# reed.net
KiCad netlist of a schematic drawn in EAGLE
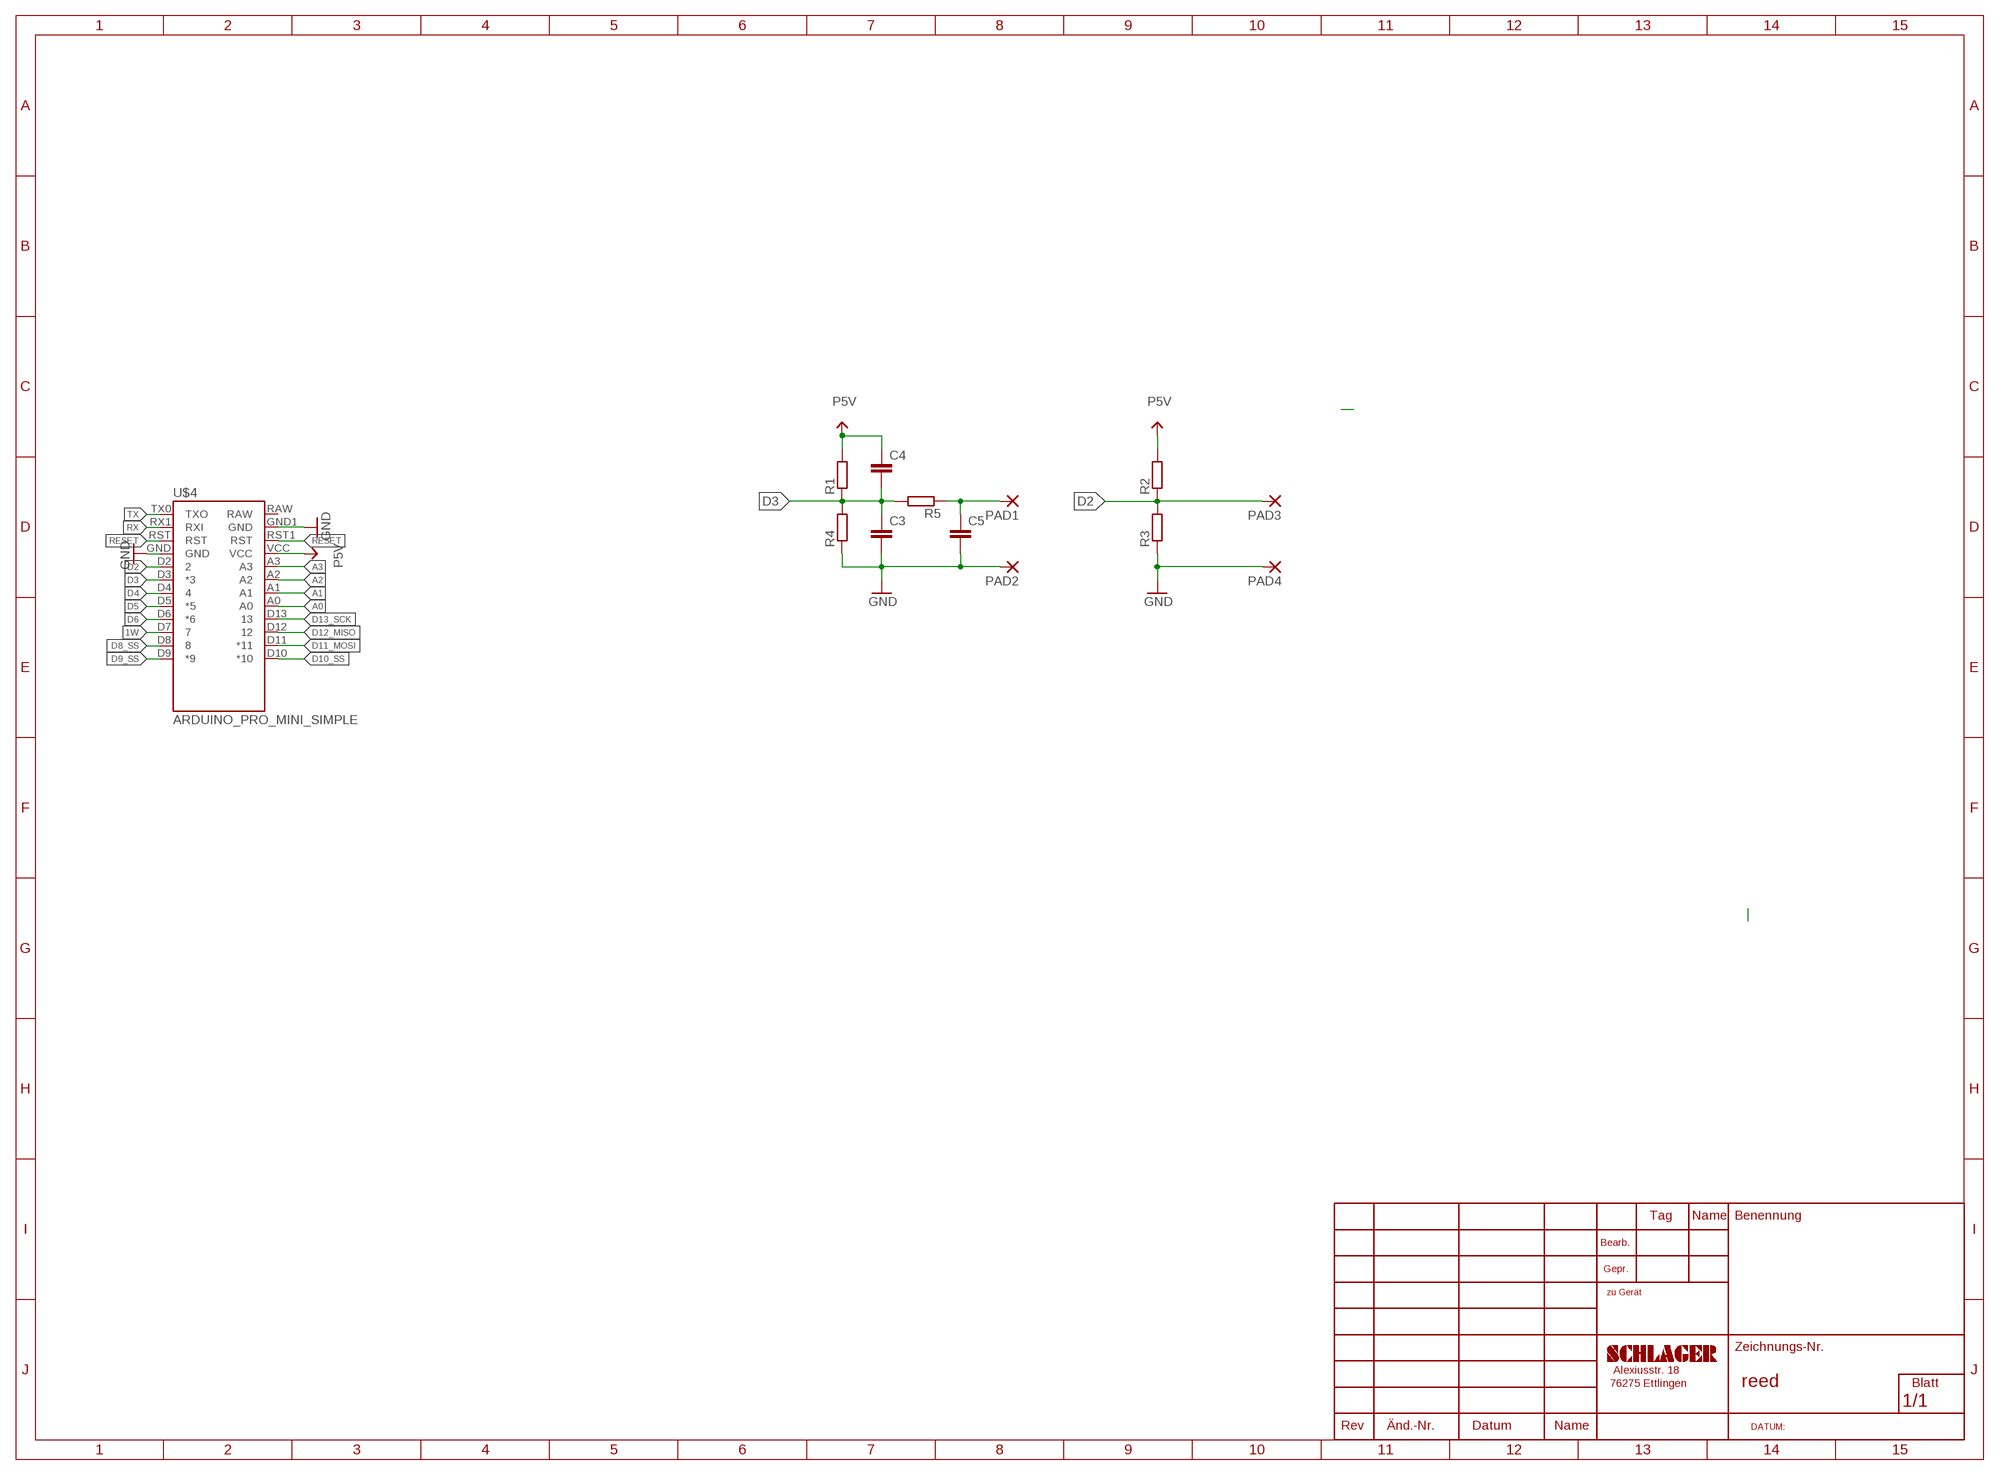
[diagram p0: schematic, sheet 1]

(export (version "E")
  (design (tool "Eeschema 10.0.6"))
  (components
    (comp (ref "C3")
      (value "C-EUC0603K")
      (footprint "eagle-import:C0603K")
      (libsource (lib "eagle-import") (part "C-EUC0603K"))
    )
    (comp (ref "C4")
      (value "C-EUC0603K")
      (footprint "eagle-import:C0603K")
      (libsource (lib "eagle-import") (part "C-EUC0603K"))
    )
    (comp (ref "C5")
      (value "C-EUC0603K")
      (footprint "eagle-import:C0603K")
      (libsource (lib "eagle-import") (part "C-EUC0603K"))
    )
    (comp (ref "PAD1")
      (value "SMD2")
      (footprint "eagle-import:SMD1,27-2,54")
      (libsource (lib "eagle-import") (part "SMD2"))
    )
    (comp (ref "PAD2")
      (value "SMD2")
      (footprint "eagle-import:SMD1,27-2,54")
      (libsource (lib "eagle-import") (part "SMD2"))
    )
    (comp (ref "PAD3")
      (value "SMD2")
      (footprint "eagle-import:SMD1,27-2,54")
      (libsource (lib "eagle-import") (part "SMD2"))
    )
    (comp (ref "PAD4")
      (value "SMD2")
      (footprint "eagle-import:SMD1,27-2,54")
      (libsource (lib "eagle-import") (part "SMD2"))
    )
    (comp (ref "R1")
      (value "R-EU_R0603")
      (footprint "eagle-import:R0603")
      (libsource (lib "eagle-import") (part "R-EU_R0603"))
    )
    (comp (ref "R2")
      (value "R-EU_R0603")
      (footprint "eagle-import:R0603")
      (libsource (lib "eagle-import") (part "R-EU_R0603"))
    )
    (comp (ref "R3")
      (value "R-EU_R0603")
      (footprint "eagle-import:R0603")
      (libsource (lib "eagle-import") (part "R-EU_R0603"))
    )
    (comp (ref "R4")
      (value "R-EU_R0603")
      (footprint "eagle-import:R0603")
      (libsource (lib "eagle-import") (part "R-EU_R0603"))
    )
    (comp (ref "R5")
      (value "R-EU_R0603")
      (footprint "eagle-import:R0603")
      (libsource (lib "eagle-import") (part "R-EU_R0603"))
    )
    (comp (ref "U$4")
      (value "ARDUINO_PRO_MINI_SIMPLE")
      (footprint "eagle-import:PRO_MINI_SIMPLE")
      (libsource (lib "eagle-import") (part "ARDUINO_PRO_MINI_SIMPLE"))
    )
  )
  (nets
    (net (code "1") (name "1W") (class "Default")
      (node (ref "U$4") (pin "D7") (pinfunction "7_D7") (pintype "bidirectional"))
    )
    (net (code "2") (name "A0") (class "Default")
      (node (ref "U$4") (pin "A0") (pinfunction "A0_A0") (pintype "bidirectional"))
    )
    (net (code "3") (name "A1") (class "Default")
      (node (ref "U$4") (pin "A1") (pinfunction "A1_A1") (pintype "bidirectional"))
    )
    (net (code "4") (name "A2") (class "Default")
      (node (ref "U$4") (pin "A2") (pinfunction "A2_A2") (pintype "bidirectional"))
    )
    (net (code "5") (name "A3") (class "Default")
      (node (ref "U$4") (pin "A3") (pinfunction "A3_A3") (pintype "bidirectional"))
    )
    (net (code "6") (name "D2") (class "Default")
      (node (ref "PAD3") (pin "1") (pinfunction "P_1") (pintype "passive"))
      (node (ref "R2") (pin "1") (pinfunction "1_1") (pintype "passive"))
      (node (ref "R3") (pin "2") (pinfunction "2_2") (pintype "passive"))
      (node (ref "U$4") (pin "D2") (pinfunction "2_D2") (pintype "bidirectional"))
    )
    (net (code "7") (name "D3") (class "Default")
      (node (ref "C3") (pin "1") (pinfunction "1_1") (pintype "passive"))
      (node (ref "C4") (pin "2") (pinfunction "2_2") (pintype "passive"))
      (node (ref "R1") (pin "1") (pinfunction "1_1") (pintype "passive"))
      (node (ref "R4") (pin "2") (pinfunction "2_2") (pintype "passive"))
      (node (ref "R5") (pin "2") (pinfunction "2_2") (pintype "passive"))
      (node (ref "U$4") (pin "D3") (pinfunction "*3_D3") (pintype "bidirectional"))
    )
    (net (code "8") (name "D4") (class "Default")
      (node (ref "U$4") (pin "D4") (pinfunction "4_D4") (pintype "bidirectional"))
    )
    (net (code "9") (name "D5") (class "Default")
      (node (ref "U$4") (pin "D5") (pinfunction "*5_D5") (pintype "bidirectional"))
    )
    (net (code "10") (name "D6") (class "Default")
      (node (ref "U$4") (pin "D6") (pinfunction "*6_D6") (pintype "bidirectional"))
    )
    (net (code "11") (name "D8_SS") (class "Default")
      (node (ref "U$4") (pin "D8") (pinfunction "8_D8") (pintype "bidirectional"))
    )
    (net (code "12") (name "D9_SS") (class "Default")
      (node (ref "U$4") (pin "D9") (pinfunction "*9_D9") (pintype "bidirectional"))
    )
    (net (code "13") (name "D10_SS") (class "Default")
      (node (ref "U$4") (pin "D10") (pinfunction "*10_D10") (pintype "bidirectional"))
    )
    (net (code "14") (name "D11_MOSI") (class "Default")
      (node (ref "U$4") (pin "D11") (pinfunction "*11_D11") (pintype "bidirectional"))
    )
    (net (code "15") (name "D12_MISO") (class "Default")
      (node (ref "U$4") (pin "D12") (pinfunction "12_D12") (pintype "bidirectional"))
    )
    (net (code "16") (name "D13_SCK") (class "Default")
      (node (ref "U$4") (pin "D13") (pinfunction "13_D13") (pintype "bidirectional"))
    )
    (net (code "17") (name "GND") (class "Default")
      (node (ref "C3") (pin "2") (pinfunction "2_2") (pintype "passive"))
      (node (ref "C5") (pin "2") (pinfunction "2_2") (pintype "passive"))
      (node (ref "PAD2") (pin "1") (pinfunction "P_1") (pintype "passive"))
      (node (ref "PAD4") (pin "1") (pinfunction "P_1") (pintype "passive"))
      (node (ref "R3") (pin "1") (pinfunction "1_1") (pintype "passive"))
      (node (ref "R4") (pin "1") (pinfunction "1_1") (pintype "passive"))
      (node (ref "U$4") (pin "GND") (pinfunction "GND_GND") (pintype "bidirectional"))
      (node (ref "U$4") (pin "GND1") (pinfunction "GND_GND1") (pintype "bidirectional"))
    )
    (net (code "18") (name "Net-(PAD1-P)") (class "Default")
      (node (ref "C5") (pin "1") (pinfunction "1_1") (pintype "passive"))
      (node (ref "PAD1") (pin "1") (pinfunction "P_1") (pintype "passive"))
      (node (ref "R5") (pin "1") (pinfunction "1_1") (pintype "passive"))
    )
    (net (code "19") (name "P5V") (class "Default")
      (node (ref "C4") (pin "1") (pinfunction "1_1") (pintype "passive"))
      (node (ref "R1") (pin "2") (pinfunction "2_2") (pintype "passive"))
      (node (ref "R2") (pin "2") (pinfunction "2_2") (pintype "passive"))
      (node (ref "U$4") (pin "VCC") (pinfunction "VCC_VCC") (pintype "bidirectional"))
    )
    (net (code "20") (name "RESET") (class "Default")
      (node (ref "U$4") (pin "RST") (pinfunction "RST_RST") (pintype "bidirectional"))
      (node (ref "U$4") (pin "RST1") (pinfunction "RST_RST1") (pintype "bidirectional"))
    )
    (net (code "21") (name "RX") (class "Default")
      (node (ref "U$4") (pin "RX1") (pinfunction "RXI_RX1") (pintype "bidirectional"))
    )
    (net (code "22") (name "TX") (class "Default")
      (node (ref "U$4") (pin "TX0") (pinfunction "TXO_TX0") (pintype "bidirectional"))
    )
    (net (code "23") (name "unconnected-(U$4-PadRAW)") (class "Default")
      (node (ref "U$4") (pin "RAW") (pinfunction "RAW_RAW") (pintype "bidirectional"))
    )
  )
)
